# esp32_c6_a1_sensors.net
KiCad netlist of a schematic drawn in Altium Designer
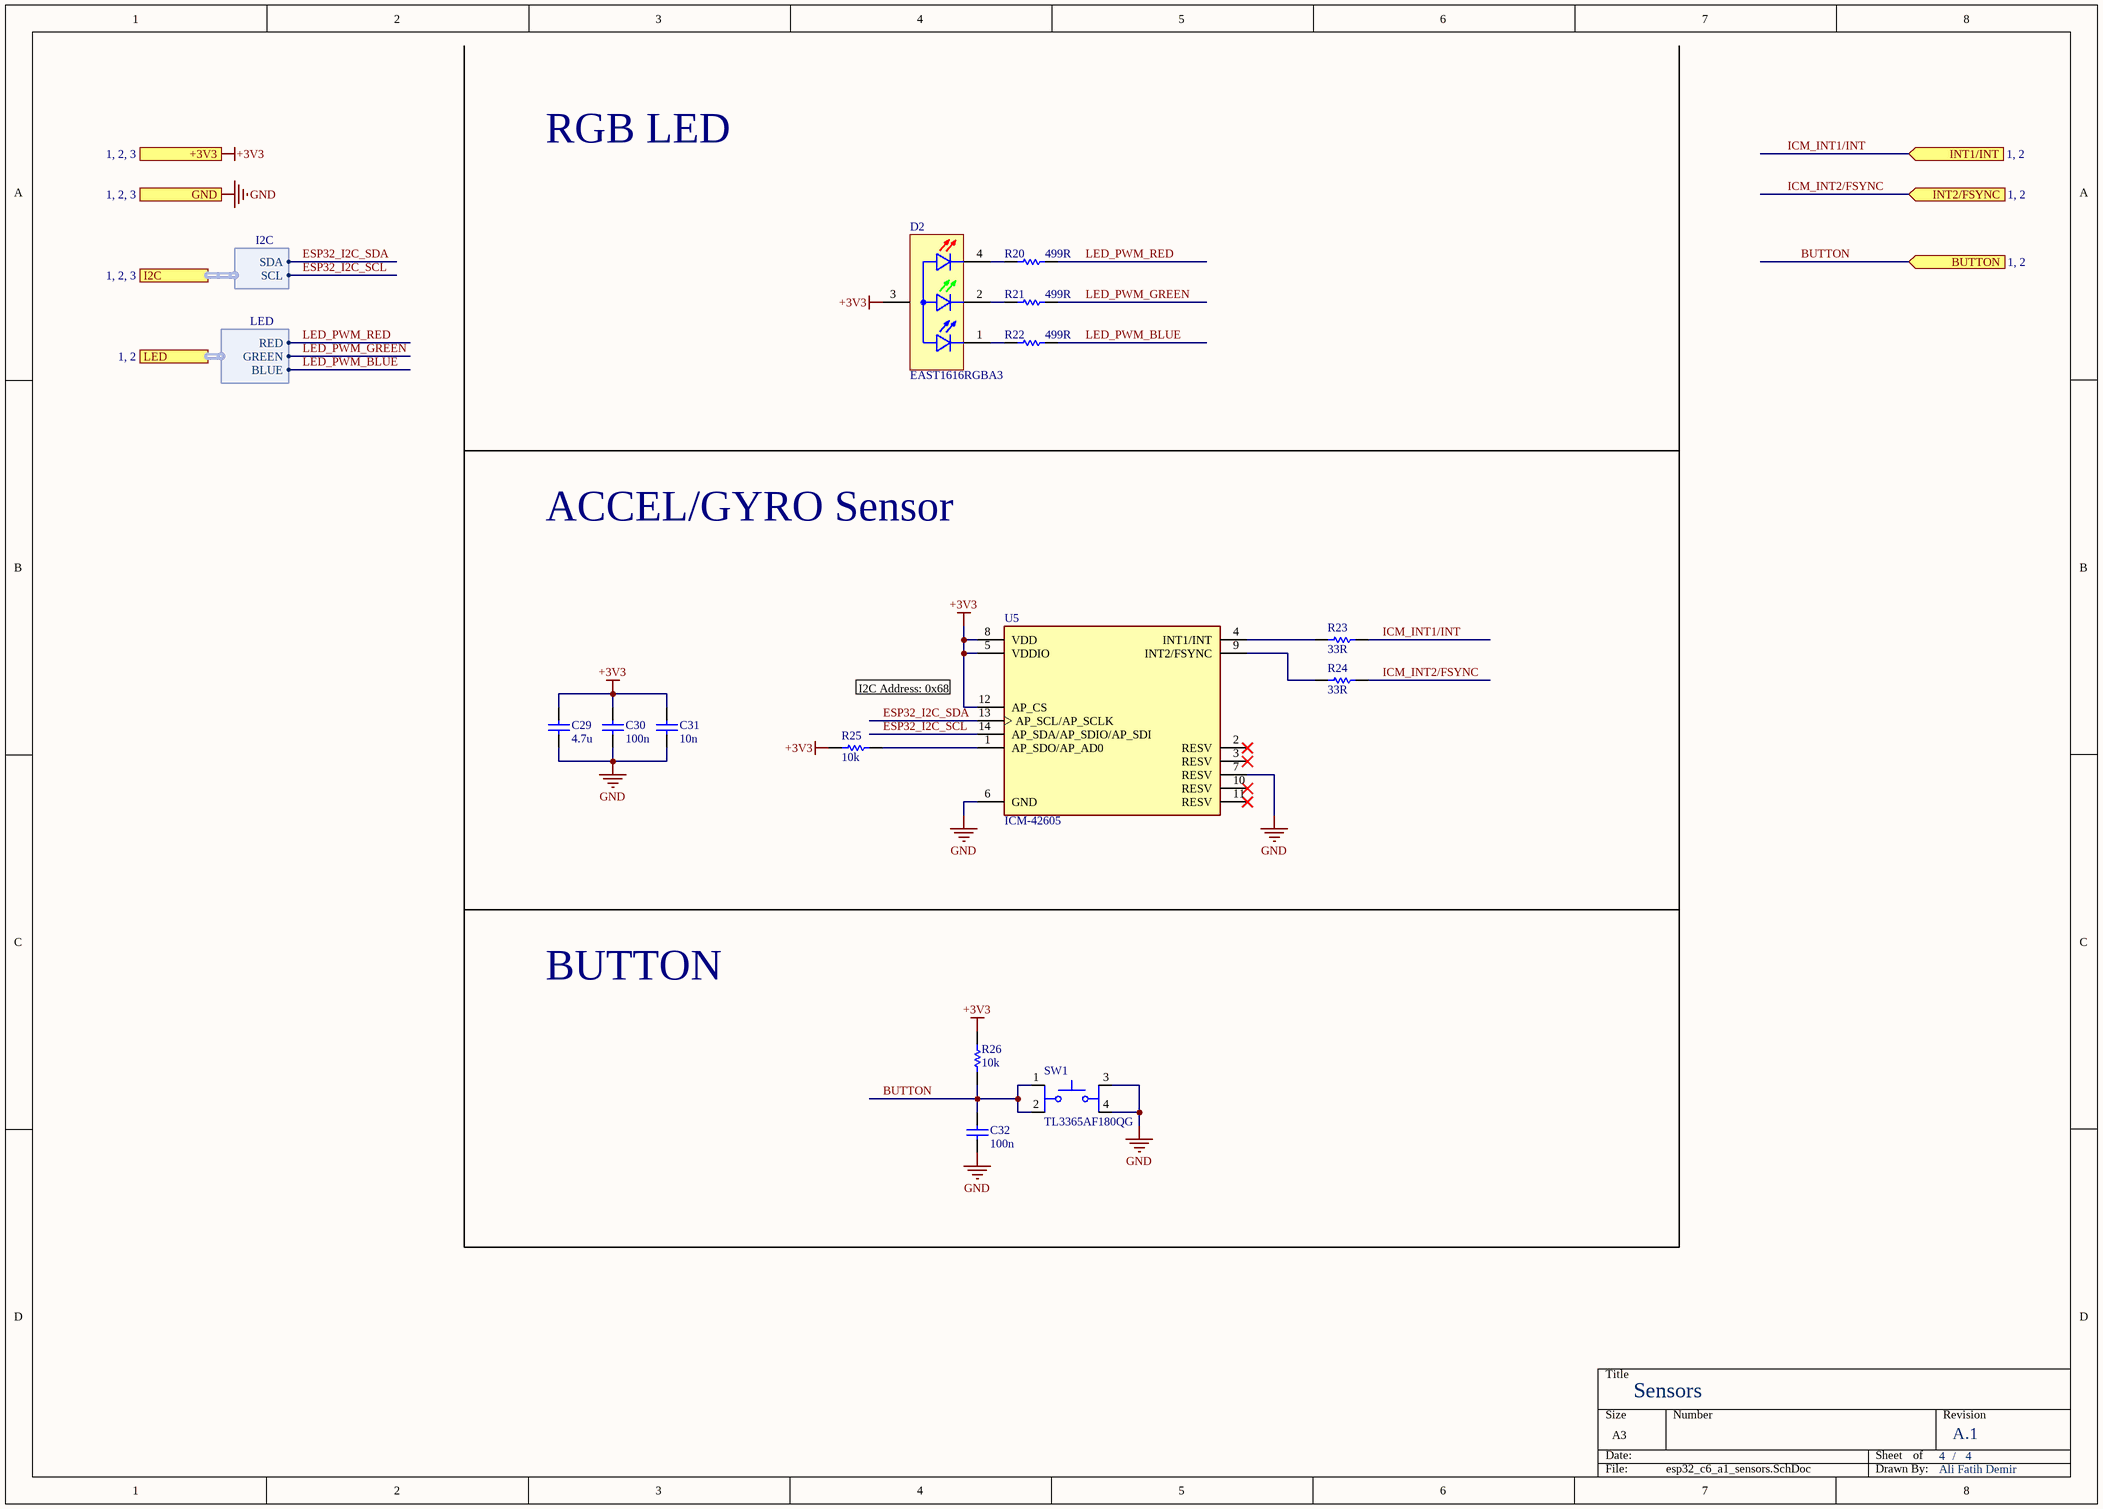
[diagram p0: esp32_c6_a1_sensors.SchDoc]

(export (version "E")
  (design (tool "Eeschema 10.0.6"))
  (components
    (comp (ref "C29")
      (value "4.7u")
      (footprint "C_0603")
      (description "SMD 0603 Ceramic Chip Capacitor")
      (fields (field (name "MANUFACTURER") "Samsung") (field (name "PART NUMBER") "?"))
      (libsource (lib "afd_lib") (part "C_0603"))
    )
    (comp (ref "C30")
      (value "100n")
      (footprint "C_0402")
      (description "SMD 0402 Ceramic Chip Capacitor")
      (fields (field (name "MANUFACTURER") "Samsung") (field (name "PART NUMBER") "?"))
      (libsource (lib "afd_lib") (part "C_0402"))
    )
    (comp (ref "C31")
      (value "10n")
      (footprint "C_0402")
      (description "SMD 0402 Ceramic Chip Capacitor")
      (fields (field (name "MANUFACTURER") "Samsung") (field (name "PART NUMBER") "?"))
      (libsource (lib "afd_lib") (part "C_0402"))
    )
    (comp (ref "C32")
      (value "100n")
      (footprint "C_0402")
      (description "SMD 0402 Ceramic Chip Capacitor")
      (fields (field (name "MANUFACTURER") "Samsung") (field (name "PART NUMBER") "?"))
      (libsource (lib "afd_lib") (part "C_0402"))
    )
    (comp (ref "D2")
      (value "EAST1616RGBA3")
      (footprint "LED_EAST1616RGBA3")
      (fields (field (name "MANUFACTURER") "Everlight Electronics"))
      (libsource (lib "afd_lib") (part "EAST1616RGBA3"))
    )
    (comp (ref "R20")
      (value "499R")
      (footprint "R_0402")
      (description "SMD 0402 Rectangular Thick Film Chip Resistor")
      (fields (field (name "MANUFACTURER") "Yageo") (field (name "PART NUMBER") "?"))
      (libsource (lib "afd_lib") (part "R_0402"))
    )
    (comp (ref "R21")
      (value "499R")
      (footprint "R_0402")
      (description "SMD 0402 Rectangular Thick Film Chip Resistor")
      (fields (field (name "MANUFACTURER") "Yageo") (field (name "PART NUMBER") "?"))
      (libsource (lib "afd_lib") (part "R_0402"))
    )
    (comp (ref "R22")
      (value "499R")
      (footprint "R_0402")
      (description "SMD 0402 Rectangular Thick Film Chip Resistor")
      (fields (field (name "MANUFACTURER") "Yageo") (field (name "PART NUMBER") "?"))
      (libsource (lib "afd_lib") (part "R_0402"))
    )
    (comp (ref "R23")
      (value "33R")
      (footprint "R_0402")
      (description "SMD 0402 Rectangular Thick Film Chip Resistor")
      (fields (field (name "MANUFACTURER") "Yageo") (field (name "PART NUMBER") "?"))
      (libsource (lib "afd_lib") (part "R_0402"))
    )
    (comp (ref "R24")
      (value "33R")
      (footprint "R_0402")
      (description "SMD 0402 Rectangular Thick Film Chip Resistor")
      (fields (field (name "MANUFACTURER") "Yageo") (field (name "PART NUMBER") "?"))
      (libsource (lib "afd_lib") (part "R_0402"))
    )
    (comp (ref "R25")
      (value "10k")
      (footprint "R_0402")
      (description "SMD 0402 Rectangular Thick Film Chip Resistor")
      (fields (field (name "MANUFACTURER") "Yageo") (field (name "PART NUMBER") "?"))
      (libsource (lib "afd_lib") (part "R_0402"))
    )
    (comp (ref "R26")
      (value "10k")
      (footprint "R_0402")
      (description "SMD 0402 Rectangular Thick Film Chip Resistor")
      (fields (field (name "MANUFACTURER") "Yageo") (field (name "PART NUMBER") "?"))
      (libsource (lib "afd_lib") (part "R_0402"))
    )
    (comp (ref "SW1")
      (value "TL3365AF180QG")
      (footprint "SW_TL3365AF180QG")
      (description "Tactile Switch SPST-NO Top Actuated Surface Mount")
      (fields (field (name "MANUFACTURER") "E-Switch"))
      (libsource (lib "afd_lib") (part "TL3365AF180QG"))
    )
    (comp (ref "U5")
      (value "ICM-42605")
      (footprint "XDCR_ICM-42605")
      (description "Accelerometer, Gyroscope, 6 Axis Sensor I2C, I3C, SPI Output")
      (fields (field (name "MANUFACTURER") "TDK Invensense"))
      (libsource (lib "afd_lib") (part "ICM-42605"))
    )
  )
  (nets
    (net (code "3") (name "+3V3") (class "Default")
      (node (ref "C29") (pin "2") (pinfunction "2_2") (pintype "passive"))
      (node (ref "C30") (pin "1") (pinfunction "1_1") (pintype "passive"))
      (node (ref "C31") (pin "1") (pinfunction "1_1") (pintype "passive"))
      (node (ref "D2") (pin "3") (pinfunction "A_3") (pintype "passive"))
      (node (ref "R25") (pin "2") (pinfunction "2_2") (pintype "passive"))
      (node (ref "R26") (pin "1") (pinfunction "1_1") (pintype "passive"))
      (node (ref "U5") (pin "12") (pinfunction "AP_CS_12") (pintype "passive"))
      (node (ref "U5") (pin "5") (pinfunction "VDDIO_5") (pintype "passive"))
      (node (ref "U5") (pin "8") (pinfunction "VDD_8") (pintype "passive"))
    )
    (net (code "4") (name "/BUTTON") (class "Default")
      (node (ref "C32") (pin "1") (pinfunction "1_1") (pintype "passive"))
      (node (ref "R26") (pin "2") (pinfunction "2_2") (pintype "passive"))
      (node (ref "SW1") (pin "1") (pinfunction "1_1") (pintype "passive"))
      (node (ref "SW1") (pin "2") (pinfunction "2_2") (pintype "passive"))
    )
    (net (code "5") (name "/ESP32_I2C_SCL") (class "Default")
      (node (ref "U5") (pin "14") (pinfunction "AP_SDA/AP_SDIO/AP_SDI_14") (pintype "passive"))
    )
    (net (code "6") (name "/ESP32_I2C_SDA") (class "Default")
      (node (ref "U5") (pin "13") (pinfunction "AP_SCL/AP_SCLK_13") (pintype "passive"))
    )
    (net (code "7") (name "/ICM_INT1{slash}INT") (class "Default")
      (node (ref "R23") (pin "1") (pinfunction "1_1") (pintype "passive"))
    )
    (net (code "8") (name "/ICM_INT2{slash}FSYNC") (class "Default")
      (node (ref "R24") (pin "1") (pinfunction "1_1") (pintype "passive"))
    )
    (net (code "9") (name "/LED_PWM_BLUE") (class "Default")
      (node (ref "R22") (pin "2") (pinfunction "2_2") (pintype "passive"))
    )
    (net (code "10") (name "/LED_PWM_GREEN") (class "Default")
      (node (ref "R21") (pin "2") (pinfunction "2_2") (pintype "passive"))
    )
    (net (code "11") (name "/LED_PWM_RED") (class "Default")
      (node (ref "R20") (pin "2") (pinfunction "2_2") (pintype "passive"))
    )
    (net (code "14") (name "GND") (class "Default")
      (node (ref "C29") (pin "1") (pinfunction "1_1") (pintype "passive"))
      (node (ref "C30") (pin "2") (pinfunction "2_2") (pintype "passive"))
      (node (ref "C31") (pin "2") (pinfunction "2_2") (pintype "passive"))
      (node (ref "C32") (pin "2") (pinfunction "2_2") (pintype "passive"))
      (node (ref "SW1") (pin "3") (pinfunction "3_3") (pintype "passive"))
      (node (ref "SW1") (pin "4") (pinfunction "4_4") (pintype "passive"))
      (node (ref "U5") (pin "6") (pinfunction "GND_6") (pintype "passive"))
      (node (ref "U5") (pin "7") (pinfunction "RESV_7") (pintype "passive"))
    )
    (net (code "15") (name "Net-(D2-B_C)") (class "Default")
      (node (ref "D2") (pin "1") (pinfunction "B_C_1") (pintype "passive"))
      (node (ref "R22") (pin "1") (pinfunction "1_1") (pintype "passive"))
    )
    (net (code "16") (name "Net-(D2-G_C)") (class "Default")
      (node (ref "D2") (pin "2") (pinfunction "G_C_2") (pintype "passive"))
      (node (ref "R21") (pin "1") (pinfunction "1_1") (pintype "passive"))
    )
    (net (code "17") (name "Net-(D2-R_C)") (class "Default")
      (node (ref "D2") (pin "4") (pinfunction "R_C_4") (pintype "passive"))
      (node (ref "R20") (pin "1") (pinfunction "1_1") (pintype "passive"))
    )
    (net (code "18") (name "Net-(U5-AP_SDO{slash}AP_AD0)") (class "Default")
      (node (ref "R25") (pin "1") (pinfunction "1_1") (pintype "passive"))
      (node (ref "U5") (pin "1") (pinfunction "AP_SDO/AP_AD0_1") (pintype "passive"))
    )
    (net (code "19") (name "Net-(U5-INT1{slash}INT)") (class "Default")
      (node (ref "R23") (pin "2") (pinfunction "2_2") (pintype "passive"))
      (node (ref "U5") (pin "4") (pinfunction "INT1/INT_4") (pintype "passive"))
    )
    (net (code "20") (name "Net-(U5-INT2{slash}FSYNC)") (class "Default")
      (node (ref "R24") (pin "2") (pinfunction "2_2") (pintype "passive"))
      (node (ref "U5") (pin "9") (pinfunction "INT2/FSYNC_9") (pintype "passive"))
    )
    (net (code "21") (name "unconnected-(U5-RESV-Pad2)") (class "Default")
      (node (ref "U5") (pin "2") (pinfunction "RESV_2") (pintype "passive+no_connect"))
    )
    (net (code "22") (name "unconnected-(U5-RESV-Pad3)") (class "Default")
      (node (ref "U5") (pin "3") (pinfunction "RESV_3") (pintype "passive+no_connect"))
    )
    (net (code "23") (name "unconnected-(U5-RESV-Pad10)") (class "Default")
      (node (ref "U5") (pin "10") (pinfunction "RESV_10") (pintype "passive+no_connect"))
    )
    (net (code "24") (name "unconnected-(U5-RESV-Pad11)") (class "Default")
      (node (ref "U5") (pin "11") (pinfunction "RESV_11") (pintype "passive+no_connect"))
    )
  )
)
